# Isolation_Rev2.net
KiCad netlist of a schematic drawn in Altium Designer
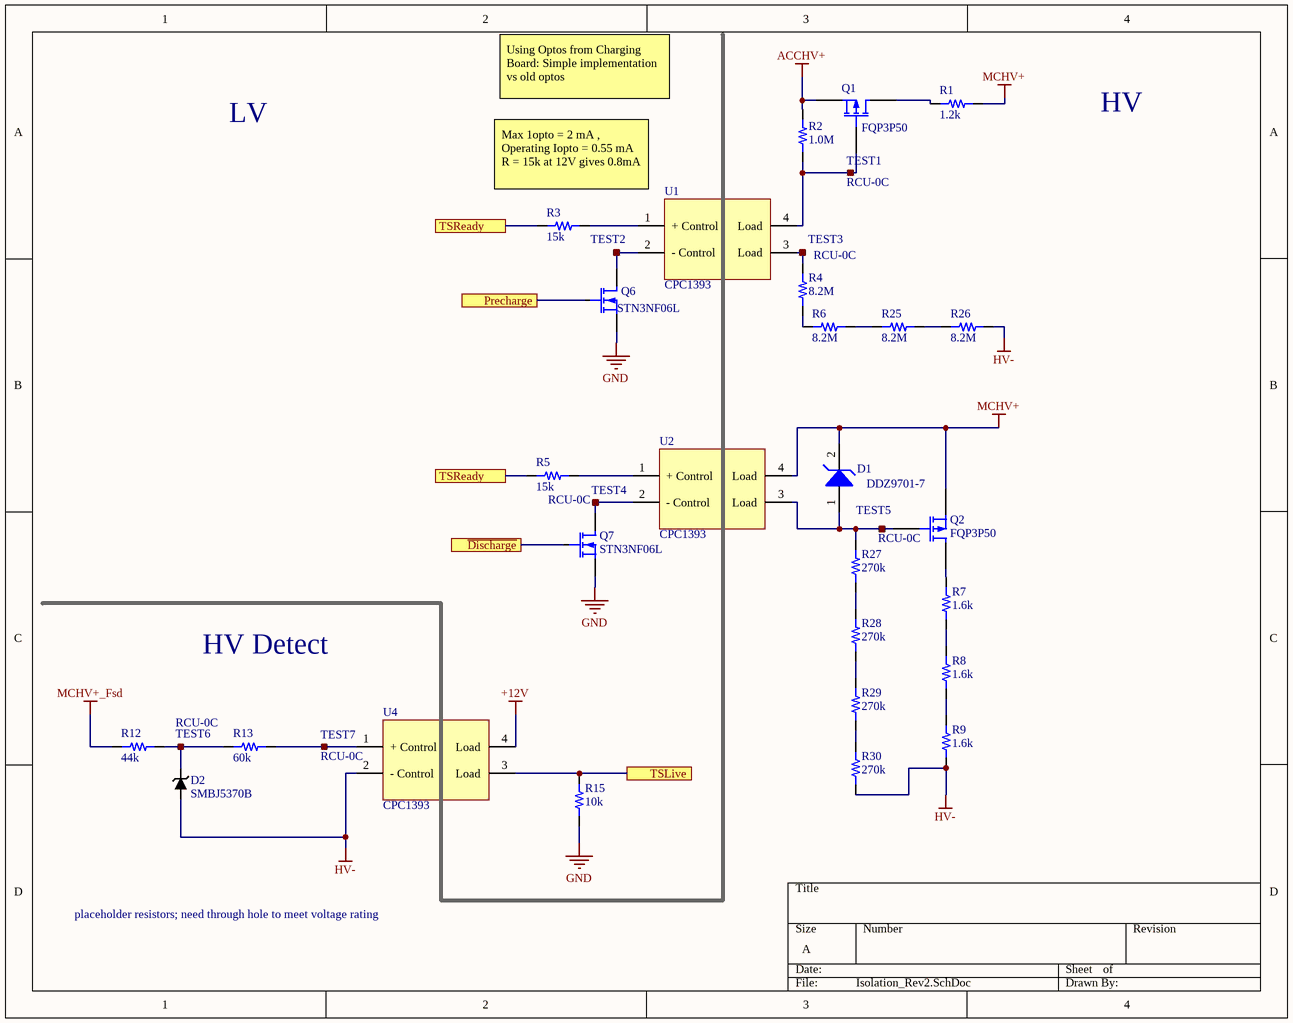
[diagram p0: Isolation_Rev2.SchDoc]

(export (version "E")
  (design (tool "Eeschema 10.0.6"))
  (components
    (comp (ref "D1")
      (value "DDZ9701-7")
      (footprint "SOD123F")
      (description "Zener Diode 14V 500mW ±5% Surface Mount SOD-123")
      (fields (field (name "POWER") "500mW"))
      (libsource (lib "Altium-Lib") (part "Zener"))
    )
    (comp (ref "D2")
      (value "SMBJ5370B")
      (footprint "SMBJ5370B-TP")
      (description "56V Zener Diode")
      (fields (field (name "CREATED_BY") "Graydon"))
      (libsource (lib "Altium-Lib") (part "SMBJ5370B-TP"))
    )
    (comp (ref "Q1")
      (value "FQP3P50")
      (footprint "TO-220AB")
      (fields (field (name "CREATED_BY") "Angel"))
      (libsource (lib "Altium-Lib") (part "FQP3P50"))
    )
    (comp (ref "Q2")
      (value "FQP3P50")
      (footprint "TO-220AB")
      (fields (field (name "CREATED_BY") "Angel"))
      (libsource (lib "Altium-Lib") (part "FQP3P50"))
    )
    (comp (ref "Q6")
      (value "STN3NF06L")
      (footprint "STN3NF06L")
      (description "MOSFET N-CH 60V 4A SOT223")
      (fields (field (name "CREATED_BY") "Graydon"))
      (libsource (lib "Altium-Lib") (part "STN3NF06L"))
    )
    (comp (ref "Q7")
      (value "STN3NF06L")
      (footprint "STN3NF06L")
      (description "MOSFET N-CH 60V 4A SOT223")
      (fields (field (name "CREATED_BY") "Graydon"))
      (libsource (lib "Altium-Lib") (part "STN3NF06L"))
    )
    (comp (ref "R1")
      (value "1.2k")
      (footprint "AP101")
      (description "100W Throughhole Resistor")
      (fields
        (field (name "TOLERANCE") "5%")
        (field (name "POWER") "100W")
        (field (name "CREATED_BY") "Graydon")
      )
      (libsource (lib "Altium-Lib") (part "Resistor"))
    )
    (comp (ref "R2")
      (value "1.0M")
      (footprint "RES 0603/1608")
      (fields
        (field (name "TOLERANCE") "10%")
        (field (name "POWER") "1/10W")
        (field (name "Comment") "Resistor 1.0M 0603 1/10W 10%")
        (field (name "CREATED_BY") "Nick Mah")
      )
      (libsource (lib "Altium-Lib") (part "Resistor"))
    )
    (comp (ref "R3")
      (value "15k")
      (footprint "RES 0603/1608")
      (fields
        (field (name "TOLERANCE") "1%")
        (field (name "POWER") "1/10W")
        (field (name "Comment") "Resistor 3.0k 0603 1/10W 1%")
        (field (name "CREATED_BY") "Nick Mah")
      )
      (libsource (lib "Altium-Lib") (part "Resistor"))
    )
    (comp (ref "R4")
      (value "8.2M")
      (footprint "RES 0805/2012")
      (fields
        (field (name "TOLERANCE") "5%")
        (field (name "POWER") "1/4W")
        (field (name "Comment") "Resistor 8.2M 0805 1/4W 5%")
        (field (name "CREATED_BY") "Nick Mah")
      )
      (libsource (lib "Altium-Lib") (part "Resistor"))
    )
    (comp (ref "R5")
      (value "15k")
      (footprint "RES 0603/1608")
      (fields
        (field (name "TOLERANCE") "1%")
        (field (name "POWER") "1/10W")
        (field (name "Comment") "Resistor 3.0k 0603 1/10W 1%")
        (field (name "CREATED_BY") "Nick Mah")
      )
      (libsource (lib "Altium-Lib") (part "Resistor"))
    )
    (comp (ref "R6")
      (value "8.2M")
      (footprint "RES 0805/2012")
      (fields
        (field (name "TOLERANCE") "5%")
        (field (name "POWER") "1/4W")
        (field (name "Comment") "Resistor 8.2M 0805 1/4W 5%")
        (field (name "CREATED_BY") "Nick Mah")
      )
      (libsource (lib "Altium-Lib") (part "Resistor"))
    )
    (comp (ref "R7")
      (value "1.6k")
      (footprint "Axial 52mm Pitch")
      (fields
        (field (name "TOLERANCE") "5%")
        (field (name "POWER") "10W")
        (field (name "MFRPARTNO") "SQP10AJB-1K6")
      )
      (libsource (lib "Altium-Lib") (part "Resistor"))
    )
    (comp (ref "R8")
      (value "1.6k")
      (footprint "Axial 52mm Pitch")
      (fields
        (field (name "TOLERANCE") "5%")
        (field (name "POWER") "10W")
        (field (name "MFRPARTNO") "SQP10AJB-1K6")
      )
      (libsource (lib "Altium-Lib") (part "Resistor"))
    )
    (comp (ref "R9")
      (value "1.6k")
      (footprint "Axial 52mm Pitch")
      (fields
        (field (name "TOLERANCE") "5%")
        (field (name "POWER") "10W")
        (field (name "MFRPARTNO") "SQP10AJB-1K6")
      )
      (libsource (lib "Altium-Lib") (part "Resistor"))
    )
    (comp (ref "R12")
      (value "44k")
      (footprint "Axial 25.4mm Pitch")
      (description "2W TH resistor")
      (fields
        (field (name "TOLERANCE") "5%")
        (field (name "POWER") "2W")
        (field (name "CREATED_BY") "Graydon")
      )
      (libsource (lib "Altium-Lib") (part "Resistor"))
    )
    (comp (ref "R13")
      (value "60k")
      (footprint "Axial 25.4mm Pitch")
      (description "2W TH resistor")
      (fields
        (field (name "TOLERANCE") "5%")
        (field (name "POWER") "2W")
        (field (name "CREATED_BY") "Graydon")
      )
      (libsource (lib "Altium-Lib") (part "Resistor"))
    )
    (comp (ref "R15")
      (value "10k")
      (footprint "RES 0603/1608")
      (fields
        (field (name "TOLERANCE") "5%")
        (field (name "POWER") "1/10W")
        (field (name "Comment") "Resistor 4.7k 0603 1/10W 5%")
        (field (name "CREATED_BY") "Nick Mah")
      )
      (libsource (lib "Altium-Lib") (part "Resistor"))
    )
    (comp (ref "R25")
      (value "8.2M")
      (footprint "RES 0805/2012")
      (fields
        (field (name "TOLERANCE") "5%")
        (field (name "POWER") "1/4W")
        (field (name "Comment") "Resistor 8.2M 0805 1/4W 5%")
        (field (name "CREATED_BY") "Nick Mah")
      )
      (libsource (lib "Altium-Lib") (part "Resistor"))
    )
    (comp (ref "R26")
      (value "8.2M")
      (footprint "RES 0805/2012")
      (fields
        (field (name "TOLERANCE") "5%")
        (field (name "POWER") "1/4W")
        (field (name "Comment") "Resistor 8.2M 0805 1/4W 5%")
        (field (name "CREATED_BY") "Nick Mah")
      )
      (libsource (lib "Altium-Lib") (part "Resistor"))
    )
    (comp (ref "R27")
      (value "270k")
      (footprint "RES 0805/2012")
      (fields
        (field (name "TOLERANCE") "5%")
        (field (name "POWER") "1/4W")
        (field (name "Comment") "Resistor 270k 0805 1/4W 5%")
        (field (name "CREATED_BY") "Nick Mah")
      )
      (libsource (lib "Altium-Lib") (part "Resistor"))
    )
    (comp (ref "R28")
      (value "270k")
      (footprint "RES 0805/2012")
      (fields
        (field (name "TOLERANCE") "5%")
        (field (name "POWER") "1/4W")
        (field (name "Comment") "Resistor 270k 0805 1/4W 5%")
        (field (name "CREATED_BY") "Nick Mah")
      )
      (libsource (lib "Altium-Lib") (part "Resistor"))
    )
    (comp (ref "R29")
      (value "270k")
      (footprint "RES 0805/2012")
      (fields
        (field (name "TOLERANCE") "5%")
        (field (name "POWER") "1/4W")
        (field (name "Comment") "Resistor 270k 0805 1/4W 5%")
        (field (name "CREATED_BY") "Nick Mah")
      )
      (libsource (lib "Altium-Lib") (part "Resistor"))
    )
    (comp (ref "R30")
      (value "270k")
      (footprint "RES 0805/2012")
      (fields
        (field (name "TOLERANCE") "5%")
        (field (name "POWER") "1/4W")
        (field (name "Comment") "Resistor 270k 0805 1/4W 5%")
        (field (name "CREATED_BY") "Nick Mah")
      )
      (libsource (lib "Altium-Lib") (part "Resistor"))
    )
    (comp (ref "TEST1")
      (value "RCU-0C")
      (footprint "RCU-0C")
      (description "Test point")
      (fields (field (name "CREATED_BY") "Graydon") (field (name "UPDATED_BY") "Null"))
      (libsource (lib "Altium-Lib") (part "RCU-0C"))
    )
    (comp (ref "TEST2")
      (value "~")
      (footprint "RCU-0C")
      (description "Test point")
      (fields
        (field (name "MFRPARTNO") "RCU-0C")
        (field (name "CREATED_BY") "Graydon")
        (field (name "UPDATED_BY") "Null")
      )
      (libsource (lib "Altium-Lib") (part "RCU-0C"))
    )
    (comp (ref "TEST3")
      (value "RCU-0C")
      (footprint "RCU-0C")
      (description "Test point")
      (fields (field (name "CREATED_BY") "Graydon") (field (name "UPDATED_BY") "Null"))
      (libsource (lib "Altium-Lib") (part "RCU-0C"))
    )
    (comp (ref "TEST4")
      (value "RCU-0C")
      (footprint "RCU-0C")
      (description "Test point")
      (fields (field (name "CREATED_BY") "Graydon") (field (name "UPDATED_BY") "Null"))
      (libsource (lib "Altium-Lib") (part "RCU-0C"))
    )
    (comp (ref "TEST5")
      (value "RCU-0C")
      (footprint "RCU-0C")
      (description "Test point")
      (fields (field (name "CREATED_BY") "Graydon") (field (name "UPDATED_BY") "Null"))
      (libsource (lib "Altium-Lib") (part "RCU-0C"))
    )
    (comp (ref "TEST6")
      (value "RCU-0C")
      (footprint "RCU-0C")
      (description "Test point")
      (fields (field (name "CREATED_BY") "Graydon") (field (name "UPDATED_BY") "Null"))
      (libsource (lib "Altium-Lib") (part "RCU-0C"))
    )
    (comp (ref "TEST7")
      (value "RCU-0C")
      (footprint "RCU-0C")
      (description "Test point")
      (fields (field (name "CREATED_BY") "Graydon") (field (name "UPDATED_BY") "Null"))
      (libsource (lib "Altium-Lib") (part "RCU-0C"))
    )
    (comp (ref "U1")
      (value "CPC1393")
      (footprint "CPC1393GR")
      (description "Solid State Relay SPST-NO (1 Form A) 4-SMD (0.300\", 7.62mm)")
      (fields
        (field (name "MFRPARTNO") "CPC1393GRTR")
        (field (name "CREATED_BY") "Lynette")
        (field (name "UPDATED_BY") "Null")
      )
      (libsource (lib "Altium-Lib") (part "CPC1393"))
    )
    (comp (ref "U2")
      (value "CPC1393")
      (footprint "CPC1393GR")
      (description "Solid State Relay SPST-NO (1 Form A) 4-SMD (0.300\", 7.62mm)")
      (fields
        (field (name "MFRPARTNO") "CPC1393GRTR")
        (field (name "CREATED_BY") "Lynette")
        (field (name "UPDATED_BY") "Null")
      )
      (libsource (lib "Altium-Lib") (part "CPC1393"))
    )
    (comp (ref "U4")
      (value "CPC1393")
      (footprint "CPC1393GR")
      (description "Solid State Relay SPST-NO (1 Form A) 4-SMD (0.300\", 7.62mm)")
      (fields
        (field (name "MFRPARTNO") "CPC1393GRTR")
        (field (name "CREATED_BY") "Lynette")
        (field (name "UPDATED_BY") "Null")
      )
      (libsource (lib "Altium-Lib") (part "CPC1393"))
    )
  )
  (nets
    (net (code "1") (name "+12V") (class "Default")
      (node (ref "U4") (pin "4") (pinfunction "Load_4") (pintype "passive"))
    )
    (net (code "2") (name "/Discharge") (class "Default")
      (node (ref "Q7") (pin "1") (pinfunction "G_1") (pintype "passive"))
    )
    (net (code "3") (name "/Precharge") (class "Default")
      (node (ref "Q6") (pin "1") (pinfunction "G_1") (pintype "passive"))
    )
    (net (code "4") (name "/TSLive") (class "Default")
      (node (ref "R15") (pin "2") (pinfunction "2_2") (pintype "passive"))
      (node (ref "U4") (pin "3") (pinfunction "Load_3") (pintype "passive"))
    )
    (net (code "5") (name "/TSReady") (class "Default")
      (node (ref "R3") (pin "1") (pinfunction "1_1") (pintype "passive"))
      (node (ref "R5") (pin "1") (pinfunction "1_1") (pintype "passive"))
    )
    (net (code "6") (name "ACCHV+") (class "Default")
      (node (ref "Q1") (pin "3") (pinfunction "S_3") (pintype "passive"))
      (node (ref "R2") (pin "1") (pinfunction "1_1") (pintype "passive"))
    )
    (net (code "7") (name "GND") (class "Default")
      (node (ref "Q6") (pin "3") (pinfunction "S_3") (pintype "passive"))
      (node (ref "Q7") (pin "3") (pinfunction "S_3") (pintype "passive"))
      (node (ref "R15") (pin "1") (pinfunction "1_1") (pintype "passive"))
    )
    (net (code "8") (name "HV-") (class "Default")
      (node (ref "D2") (pin "1") (pintype "power_in"))
      (node (ref "R26") (pin "1") (pinfunction "1_1") (pintype "passive"))
      (node (ref "R30") (pin "1") (pinfunction "1_1") (pintype "passive"))
      (node (ref "R9") (pin "1") (pinfunction "1_1") (pintype "passive"))
      (node (ref "U4") (pin "2") (pinfunction "-_Control_2") (pintype "passive"))
    )
    (net (code "9") (name "MCHV+") (class "Default")
      (node (ref "D1") (pin "2") (pinfunction "K_2") (pintype "passive"))
      (node (ref "Q2") (pin "3") (pinfunction "S_3") (pintype "passive"))
      (node (ref "R1") (pin "2") (pinfunction "2_2") (pintype "passive"))
      (node (ref "U2") (pin "4") (pinfunction "Load_4") (pintype "passive"))
    )
    (net (code "10") (name "MCHV+_Fsd") (class "Default")
      (node (ref "R12") (pin "1") (pinfunction "1_1") (pintype "passive"))
    )
    (net (code "11") (name "Net-(D1-A)") (class "Default")
      (node (ref "D1") (pin "1") (pinfunction "A_1") (pintype "passive"))
      (node (ref "Q2") (pin "1") (pinfunction "G_1") (pintype "passive"))
      (node (ref "R27") (pin "2") (pinfunction "2_2") (pintype "passive"))
      (node (ref "TEST5") (pin "1") (pintype "passive"))
      (node (ref "U2") (pin "3") (pinfunction "Load_3") (pintype "passive"))
    )
    (net (code "12") (name "Net-(D2-Pad2)") (class "Default")
      (node (ref "D2") (pin "2") (pintype "power_in"))
      (node (ref "R12") (pin "2") (pinfunction "2_2") (pintype "passive"))
      (node (ref "R13") (pin "1") (pinfunction "1_1") (pintype "passive"))
      (node (ref "TEST6") (pin "1") (pintype "passive"))
    )
    (net (code "13") (name "Net-(Q1-D)") (class "Default")
      (node (ref "Q1") (pin "2") (pinfunction "D_2") (pintype "passive"))
      (node (ref "R1") (pin "1") (pinfunction "1_1") (pintype "passive"))
    )
    (net (code "14") (name "Net-(Q1-G)") (class "Default")
      (node (ref "Q1") (pin "1") (pinfunction "G_1") (pintype "passive"))
      (node (ref "R2") (pin "2") (pinfunction "2_2") (pintype "passive"))
      (node (ref "TEST1") (pin "1") (pintype "passive"))
      (node (ref "U1") (pin "4") (pinfunction "Load_4") (pintype "passive"))
    )
    (net (code "15") (name "Net-(Q2-D)") (class "Default")
      (node (ref "Q2") (pin "2") (pinfunction "D_2") (pintype "passive"))
      (node (ref "R7") (pin "2") (pinfunction "2_2") (pintype "passive"))
    )
    (net (code "16") (name "Net-(Q6-D)") (class "Default")
      (node (ref "Q6") (pin "2") (pinfunction "D_2") (pintype "passive"))
      (node (ref "TEST2") (pin "1") (pintype "passive"))
      (node (ref "U1") (pin "2") (pinfunction "-_Control_2") (pintype "passive"))
    )
    (net (code "17") (name "Net-(Q7-D)") (class "Default")
      (node (ref "Q7") (pin "2") (pinfunction "D_2") (pintype "passive"))
      (node (ref "TEST4") (pin "1") (pintype "passive"))
      (node (ref "U2") (pin "2") (pinfunction "-_Control_2") (pintype "passive"))
    )
    (net (code "18") (name "Net-(R4-Pad1)") (class "Default")
      (node (ref "R4") (pin "1") (pinfunction "1_1") (pintype "passive"))
      (node (ref "R6") (pin "2") (pinfunction "2_2") (pintype "passive"))
    )
    (net (code "19") (name "Net-(R4-Pad2)") (class "Default")
      (node (ref "R4") (pin "2") (pinfunction "2_2") (pintype "passive"))
      (node (ref "TEST3") (pin "1") (pintype "passive"))
      (node (ref "U1") (pin "3") (pinfunction "Load_3") (pintype "passive"))
    )
    (net (code "20") (name "Net-(R7-Pad1)") (class "Default")
      (node (ref "R7") (pin "1") (pinfunction "1_1") (pintype "passive"))
      (node (ref "R8") (pin "2") (pinfunction "2_2") (pintype "passive"))
    )
    (net (code "21") (name "Net-(R8-Pad1)") (class "Default")
      (node (ref "R8") (pin "1") (pinfunction "1_1") (pintype "passive"))
      (node (ref "R9") (pin "2") (pinfunction "2_2") (pintype "passive"))
    )
    (net (code "22") (name "Net-(R25-Pad1)") (class "Default")
      (node (ref "R25") (pin "1") (pinfunction "1_1") (pintype "passive"))
      (node (ref "R26") (pin "2") (pinfunction "2_2") (pintype "passive"))
    )
    (net (code "23") (name "Net-(R25-Pad2)") (class "Default")
      (node (ref "R25") (pin "2") (pinfunction "2_2") (pintype "passive"))
      (node (ref "R6") (pin "1") (pinfunction "1_1") (pintype "passive"))
    )
    (net (code "24") (name "Net-(R27-Pad1)") (class "Default")
      (node (ref "R27") (pin "1") (pinfunction "1_1") (pintype "passive"))
      (node (ref "R28") (pin "2") (pinfunction "2_2") (pintype "passive"))
    )
    (net (code "25") (name "Net-(R28-Pad1)") (class "Default")
      (node (ref "R28") (pin "1") (pinfunction "1_1") (pintype "passive"))
      (node (ref "R29") (pin "2") (pinfunction "2_2") (pintype "passive"))
    )
    (net (code "26") (name "Net-(R29-Pad1)") (class "Default")
      (node (ref "R29") (pin "1") (pinfunction "1_1") (pintype "passive"))
      (node (ref "R30") (pin "2") (pinfunction "2_2") (pintype "passive"))
    )
    (net (code "27") (name "Net-(U1-+_Control)") (class "Default")
      (node (ref "R3") (pin "2") (pinfunction "2_2") (pintype "passive"))
      (node (ref "U1") (pin "1") (pinfunction "+_Control_1") (pintype "passive"))
    )
    (net (code "28") (name "Net-(U2-+_Control)") (class "Default")
      (node (ref "R5") (pin "2") (pinfunction "2_2") (pintype "passive"))
      (node (ref "U2") (pin "1") (pinfunction "+_Control_1") (pintype "passive"))
    )
    (net (code "29") (name "Net-(U4-+_Control)") (class "Default")
      (node (ref "R13") (pin "2") (pinfunction "2_2") (pintype "passive"))
      (node (ref "TEST7") (pin "1") (pintype "passive"))
      (node (ref "U4") (pin "1") (pinfunction "+_Control_1") (pintype "passive"))
    )
  )
)
